# board_A500_CDTV.net
KiCad netlist of a schematic drawn in EAGLE
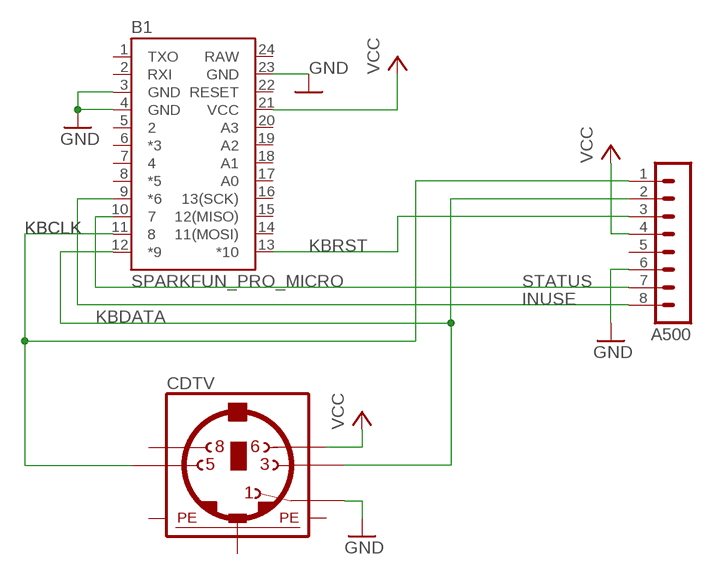
[diagram p0: schematic, sheet 1]

(export (version "E")
  (design (tool "Eeschema 10.0.6"))
  (components
    (comp (ref "A500")
      (value "MA08-1")
      (footprint "eagle-import:MA08-1")
      (libsource (lib "eagle-import") (part "MA08-1"))
    )
    (comp (ref "B1")
      (value "SPARKFUN_PRO_MICRO")
      (footprint "eagle-import:SPARKFUN_PRO_MICRO")
      (libsource (lib "eagle-import") (part "SPARKFUN_PRO_MICRO"))
    )
    (comp (ref "CDTV")
      (value "MINI_DIN_5")
      (footprint "eagle-import:M_DIN5")
      (libsource (lib "eagle-import") (part "MINI_DIN_5"))
    )
  )
  (nets
    (net (code "1") (name "/INUSE") (class "Default")
      (node (ref "A500") (pin "8") (pinfunction "8_8") (pintype "passive"))
      (node (ref "B1") (pin "9") (pinfunction "*6_9") (pintype "bidirectional"))
    )
    (net (code "2") (name "/KBCLK") (class "Default")
      (node (ref "A500") (pin "1") (pinfunction "1_1") (pintype "passive"))
      (node (ref "B1") (pin "11") (pinfunction "8_11") (pintype "bidirectional"))
      (node (ref "CDTV") (pin "5") (pinfunction "5_5") (pintype "passive"))
    )
    (net (code "3") (name "/KBDATA") (class "Default")
      (node (ref "A500") (pin "2") (pinfunction "2_2") (pintype "passive"))
      (node (ref "B1") (pin "12") (pinfunction "*9_12") (pintype "bidirectional"))
      (node (ref "CDTV") (pin "3") (pinfunction "3_3") (pintype "passive"))
    )
    (net (code "4") (name "/KBRST") (class "Default")
      (node (ref "A500") (pin "3") (pinfunction "3_3") (pintype "passive"))
      (node (ref "B1") (pin "13") (pinfunction "*10_13") (pintype "bidirectional"))
    )
    (net (code "5") (name "/PE1") (class "Default")
      (node (ref "CDTV") (pin "SH1") (pinfunction "PE1_SH1") (pintype "power_in"))
    )
    (net (code "6") (name "/PE2") (class "Default")
      (node (ref "CDTV") (pin "SH2") (pinfunction "PE2_SH2") (pintype "power_in"))
    )
    (net (code "7") (name "/PE3") (class "Default")
      (node (ref "CDTV") (pin "SH3") (pinfunction "PE3_SH3") (pintype "power_in"))
    )
    (net (code "8") (name "/RAW") (class "Default")
      (node (ref "B1") (pin "24") (pinfunction "RAW_24") (pintype "power_in"))
    )
    (net (code "9") (name "/STATUS") (class "Default")
      (node (ref "A500") (pin "7") (pinfunction "7_7") (pintype "passive"))
      (node (ref "B1") (pin "10") (pinfunction "7_10") (pintype "bidirectional"))
    )
    (net (code "10") (name "GND") (class "Default")
      (node (ref "A500") (pin "6") (pinfunction "6_6") (pintype "passive"))
      (node (ref "B1") (pin "23") (pinfunction "GND_23") (pintype "power_in"))
      (node (ref "B1") (pin "3") (pinfunction "GND_3") (pintype "power_in"))
      (node (ref "B1") (pin "4") (pinfunction "GND_4") (pintype "power_in"))
      (node (ref "CDTV") (pin "1") (pinfunction "1_1") (pintype "passive"))
    )
    (net (code "11") (name "VCC") (class "Default")
      (node (ref "A500") (pin "4") (pinfunction "4_4") (pintype "passive"))
      (node (ref "B1") (pin "21") (pinfunction "VCC_21") (pintype "power_in"))
      (node (ref "CDTV") (pin "6") (pinfunction "6_6") (pintype "passive"))
    )
    (net (code "12") (name "unconnected-(A500-Pad5)") (class "Default")
      (node (ref "A500") (pin "5") (pinfunction "5_5") (pintype "passive"))
    )
    (net (code "13") (name "unconnected-(B1-*3-Pad6)") (class "Default")
      (node (ref "B1") (pin "6") (pinfunction "*3_6") (pintype "bidirectional"))
    )
    (net (code "14") (name "unconnected-(B1-*5-Pad8)") (class "Default")
      (node (ref "B1") (pin "8") (pinfunction "*5_8") (pintype "bidirectional"))
    )
    (net (code "15") (name "unconnected-(B1-2-Pad5)") (class "Default")
      (node (ref "B1") (pin "5") (pinfunction "2_5") (pintype "bidirectional"))
    )
    (net (code "16") (name "unconnected-(B1-4-Pad7)") (class "Default")
      (node (ref "B1") (pin "7") (pinfunction "4_7") (pintype "bidirectional"))
    )
    (net (code "17") (name "unconnected-(B1-11(MOSI)-Pad14)") (class "Default")
      (node (ref "B1") (pin "14") (pinfunction "11(MOSI)_14") (pintype "bidirectional"))
    )
    (net (code "18") (name "unconnected-(B1-12(MISO)-Pad15)") (class "Default")
      (node (ref "B1") (pin "15") (pinfunction "12(MISO)_15") (pintype "bidirectional"))
    )
    (net (code "19") (name "unconnected-(B1-13(SCK)-Pad16)") (class "Default")
      (node (ref "B1") (pin "16") (pinfunction "13(SCK)_16") (pintype "bidirectional"))
    )
    (net (code "20") (name "unconnected-(B1-A0-Pad17)") (class "Default")
      (node (ref "B1") (pin "17") (pinfunction "A0_17") (pintype "bidirectional"))
    )
    (net (code "21") (name "unconnected-(B1-A1-Pad18)") (class "Default")
      (node (ref "B1") (pin "18") (pinfunction "A1_18") (pintype "bidirectional"))
    )
    (net (code "22") (name "unconnected-(B1-A2-Pad19)") (class "Default")
      (node (ref "B1") (pin "19") (pinfunction "A2_19") (pintype "bidirectional"))
    )
    (net (code "23") (name "unconnected-(B1-A3-Pad20)") (class "Default")
      (node (ref "B1") (pin "20") (pinfunction "A3_20") (pintype "bidirectional"))
    )
    (net (code "24") (name "unconnected-(B1-RESET-Pad22)") (class "Default")
      (node (ref "B1") (pin "22") (pinfunction "RESET_22") (pintype "bidirectional"))
    )
    (net (code "25") (name "unconnected-(B1-RXI-Pad2)") (class "Default")
      (node (ref "B1") (pin "2") (pinfunction "RXI_2") (pintype "bidirectional"))
    )
    (net (code "26") (name "unconnected-(B1-TXO-Pad1)") (class "Default")
      (node (ref "B1") (pin "1") (pinfunction "TXO_1") (pintype "bidirectional"))
    )
    (net (code "27") (name "unconnected-(CDTV-Pad8)") (class "Default")
      (node (ref "CDTV") (pin "8") (pinfunction "8_8") (pintype "passive"))
    )
  )
)
